# v1_5.net
KiCad netlist of a schematic drawn in EAGLE
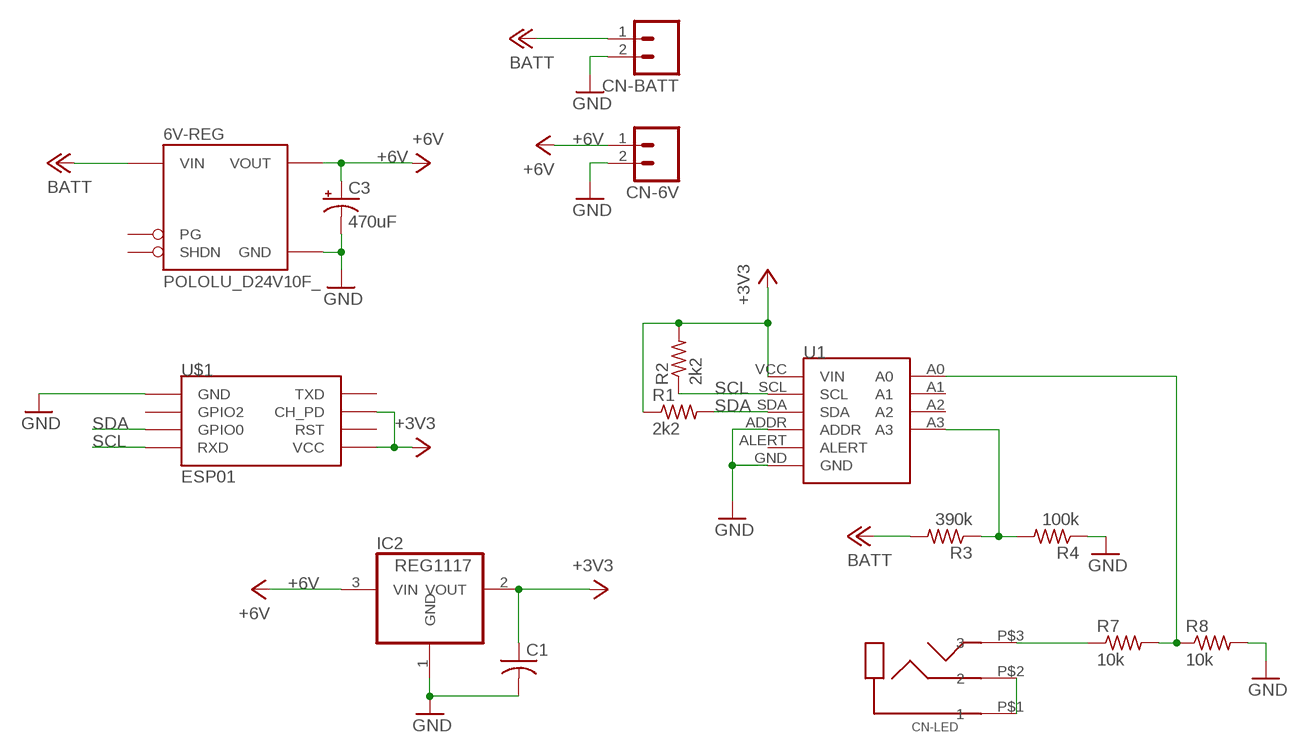
[diagram p0: schematic, sheet 1]

(export (version "E")
  (design (tool "Eeschema 10.0.6"))
  (components
    (comp (ref "6V-REG")
      (value "POLOLU_D24V10F_")
      (footprint "eagle-import:POLOLU_D24V10")
      (libsource (lib "eagle-import") (part "POLOLU_D24V10F_"))
    )
    (comp (ref "C1")
      (value "C-USC1210")
      (footprint "eagle-import:C1210")
      (libsource (lib "eagle-import") (part "C-USC1210"))
    )
    (comp (ref "C3")
      (value "470uF")
      (footprint "eagle-import:CPOL-RADIAL-2.5MM-6.5MM")
      (libsource (lib "eagle-import") (part "100UF-POLAR-RADIAL-2.5MM-25V-20%"))
    )
    (comp (ref "CN-6V")
      (value "M02")
      (footprint "eagle-import:02P")
      (libsource (lib "eagle-import") (part "M02"))
    )
    (comp (ref "CN-BATT")
      (value "M02")
      (footprint "eagle-import:02P")
      (libsource (lib "eagle-import") (part "M02"))
    )
    (comp (ref "CN-LED")
      (value "PJ-320B")
      (footprint "eagle-import:PJ-320B")
      (libsource (lib "eagle-import") (part "PJ-320B"))
    )
    (comp (ref "IC2")
      (value "REG1117")
      (footprint "eagle-import:SOT223")
      (libsource (lib "eagle-import") (part "REG1117"))
    )
    (comp (ref "R1")
      (value "2k2")
      (footprint "eagle-import:R0603")
      (libsource (lib "eagle-import") (part "R-US_R0603"))
    )
    (comp (ref "R2")
      (value "2k2")
      (footprint "eagle-import:R0603")
      (libsource (lib "eagle-import") (part "R-US_R0603"))
    )
    (comp (ref "R3")
      (value "390k")
      (footprint "eagle-import:R0603")
      (libsource (lib "eagle-import") (part "R-US_R0603"))
    )
    (comp (ref "R4")
      (value "100k")
      (footprint "eagle-import:R0603")
      (libsource (lib "eagle-import") (part "R-US_R0603"))
    )
    (comp (ref "R7")
      (value "10k")
      (footprint "eagle-import:R0603")
      (libsource (lib "eagle-import") (part "R-US_R0603"))
    )
    (comp (ref "R8")
      (value "10k")
      (footprint "eagle-import:R0603")
      (libsource (lib "eagle-import") (part "R-US_R0603"))
    )
    (comp (ref "U$1")
      (value "ESP01")
      (footprint "eagle-import:ESP01")
      (libsource (lib "eagle-import") (part "ESP01"))
    )
    (comp (ref "U1")
      (value "GY-ADS1115THM")
      (footprint "eagle-import:GY-ADS1115-THM")
      (libsource (lib "eagle-import") (part "GY-ADS1115THM"))
    )
  )
  (nets
    (net (code "1") (name "+3V3") (class "Default")
      (node (ref "C1") (pin "1") (pinfunction "1_1") (pintype "passive"))
      (node (ref "IC2") (pin "2") (pinfunction "VOUT_2") (pintype "output"))
      (node (ref "R1") (pin "1") (pinfunction "1_1") (pintype "passive"))
      (node (ref "R2") (pin "2") (pinfunction "2_2") (pintype "passive"))
      (node (ref "U$1") (pin "CH_PD") (pinfunction "CH_PD_CH_PD") (pintype "bidirectional"))
      (node (ref "U$1") (pin "VCC") (pinfunction "VCC_VCC") (pintype "bidirectional"))
      (node (ref "U1") (pin "VCC") (pinfunction "VIN_VCC") (pintype "bidirectional"))
    )
    (net (code "2") (name "+6V") (class "Default")
      (node (ref "6V-REG") (pin "VOUT") (pinfunction "VOUT_VOUT") (pintype "output"))
      (node (ref "C3") (pin "1") (pinfunction "+_1") (pintype "passive"))
      (node (ref "CN-6V") (pin "1") (pinfunction "1_1") (pintype "passive"))
      (node (ref "IC2") (pin "3") (pinfunction "VIN_3") (pintype "input"))
    )
    (net (code "3") (name "/SCL") (class "Default")
      (node (ref "R2") (pin "1") (pinfunction "1_1") (pintype "passive"))
      (node (ref "U$1") (pin "RX") (pinfunction "RXD_RX") (pintype "bidirectional"))
      (node (ref "U1") (pin "SCL") (pinfunction "SCL_SCL") (pintype "bidirectional"))
    )
    (net (code "4") (name "/SDA") (class "Default")
      (node (ref "R1") (pin "2") (pinfunction "2_2") (pintype "passive"))
      (node (ref "U$1") (pin "GPIO0") (pinfunction "GPIO0_GPIO0") (pintype "bidirectional"))
      (node (ref "U1") (pin "SDA") (pinfunction "SDA_SDA") (pintype "bidirectional"))
    )
    (net (code "5") (name "BATT") (class "Default")
      (node (ref "6V-REG") (pin "VIN") (pinfunction "VIN_VIN") (pintype "power_in"))
      (node (ref "CN-BATT") (pin "1") (pinfunction "1_1") (pintype "passive"))
      (node (ref "R3") (pin "2") (pinfunction "2_2") (pintype "passive"))
    )
    (net (code "6") (name "GND") (class "Default")
      (node (ref "6V-REG") (pin "GND") (pinfunction "GND_GND") (pintype "power_in"))
      (node (ref "C1") (pin "2") (pinfunction "2_2") (pintype "passive"))
      (node (ref "C3") (pin "2") (pinfunction "-_2") (pintype "passive"))
      (node (ref "CN-6V") (pin "2") (pinfunction "2_2") (pintype "passive"))
      (node (ref "CN-BATT") (pin "2") (pinfunction "2_2") (pintype "passive"))
      (node (ref "IC2") (pin "1") (pinfunction "GND_1") (pintype "power_in"))
      (node (ref "R4") (pin "1") (pinfunction "1_1") (pintype "passive"))
      (node (ref "R8") (pin "2") (pinfunction "2_2") (pintype "passive"))
      (node (ref "U$1") (pin "GND") (pinfunction "GND_GND") (pintype "bidirectional"))
      (node (ref "U1") (pin "ADDR") (pinfunction "ADDR_ADDR") (pintype "bidirectional"))
      (node (ref "U1") (pin "GND") (pinfunction "GND_GND") (pintype "bidirectional"))
    )
    (net (code "7") (name "Net-(CN-LED-1)") (class "Default")
      (node (ref "CN-LED") (pin "P$1") (pinfunction "1_P$1") (pintype "bidirectional"))
      (node (ref "CN-LED") (pin "P$2") (pinfunction "2_P$2") (pintype "bidirectional"))
    )
    (net (code "8") (name "Net-(CN-LED-3)") (class "Default")
      (node (ref "CN-LED") (pin "P$3") (pinfunction "3_P$3") (pintype "bidirectional"))
      (node (ref "R7") (pin "1") (pinfunction "1_1") (pintype "passive"))
    )
    (net (code "9") (name "Net-(R3-Pad1)") (class "Default")
      (node (ref "R3") (pin "1") (pinfunction "1_1") (pintype "passive"))
      (node (ref "R4") (pin "2") (pinfunction "2_2") (pintype "passive"))
      (node (ref "U1") (pin "A3") (pinfunction "A3_A3") (pintype "bidirectional"))
    )
    (net (code "10") (name "Net-(R7-Pad2)") (class "Default")
      (node (ref "R7") (pin "2") (pinfunction "2_2") (pintype "passive"))
      (node (ref "R8") (pin "1") (pinfunction "1_1") (pintype "passive"))
      (node (ref "U1") (pin "A0") (pinfunction "A0_A0") (pintype "bidirectional"))
    )
    (net (code "11") (name "unconnected-(6V-REG-PadPG)") (class "Default")
      (node (ref "6V-REG") (pin "PG") (pinfunction "PG_PG") (pintype "output"))
    )
    (net (code "12") (name "unconnected-(6V-REG-PadSHDN)") (class "Default")
      (node (ref "6V-REG") (pin "SHDN") (pinfunction "SHDN_SHDN") (pintype "input"))
    )
    (net (code "13") (name "unconnected-(U$1-PadGPIO2)") (class "Default")
      (node (ref "U$1") (pin "GPIO2") (pinfunction "GPIO2_GPIO2") (pintype "bidirectional"))
    )
    (net (code "14") (name "unconnected-(U$1-PadRST)") (class "Default")
      (node (ref "U$1") (pin "RST") (pinfunction "RST_RST") (pintype "bidirectional"))
    )
    (net (code "15") (name "unconnected-(U$1-TXD-PadTX)") (class "Default")
      (node (ref "U$1") (pin "TX") (pinfunction "TXD_TX") (pintype "bidirectional"))
    )
    (net (code "16") (name "unconnected-(U1-PadA1)") (class "Default")
      (node (ref "U1") (pin "A1") (pinfunction "A1_A1") (pintype "bidirectional"))
    )
    (net (code "17") (name "unconnected-(U1-PadA2)") (class "Default")
      (node (ref "U1") (pin "A2") (pinfunction "A2_A2") (pintype "bidirectional"))
    )
    (net (code "18") (name "unconnected-(U1-PadALERT)") (class "Default")
      (node (ref "U1") (pin "ALERT") (pinfunction "ALERT_ALERT") (pintype "bidirectional"))
    )
  )
)
